# PSU_DRIVE.net
KiCad netlist of a schematic drawn in Altium Designer
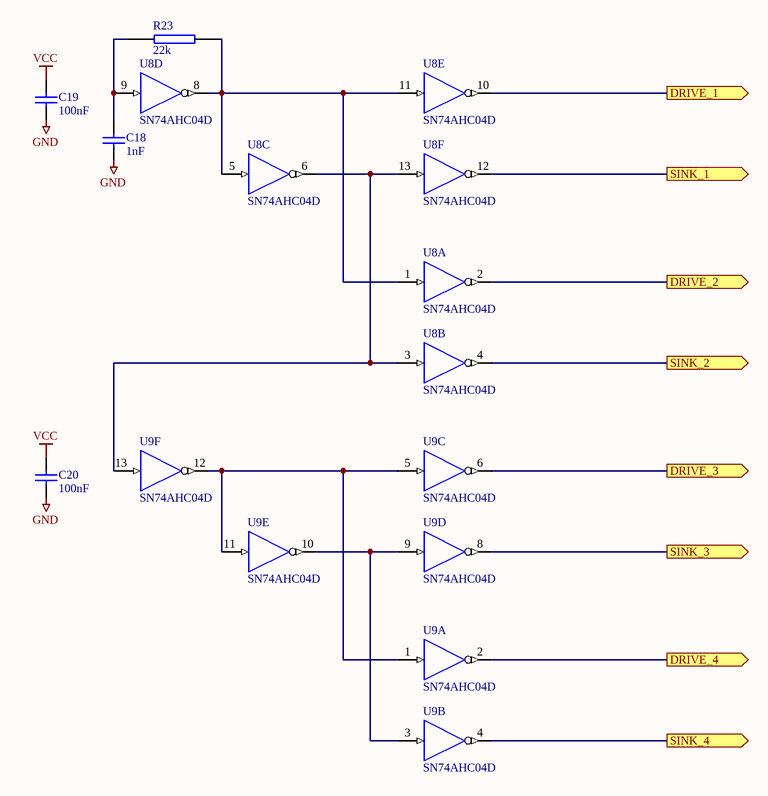
[diagram p0: PSU_DRIVE.SchDoc]

(export (version "E")
  (design (tool "Eeschema 10.0.6"))
  (components
    (comp (ref "C18")
      (value "1nF")
      (footprint "CAP (3D) - 0603")
      (description "Capacitor")
      (fields (field (name "Comment") "Cap") (field (name "PUBLISHER") "Altium Limited"))
      (libsource (lib "Miscellaneous Devices") (part "Cap"))
    )
    (comp (ref "C19")
      (value "100nF")
      (footprint "CAP (3D) - 0603")
      (description "Capacitor")
      (libsource (lib "Miscellaneous Devices") (part "Cap"))
    )
    (comp (ref "C20")
      (value "100nF")
      (footprint "CAP (3D) - 0603")
      (description "Capacitor")
      (libsource (lib "Miscellaneous Devices") (part "Cap"))
    )
    (comp (ref "R23")
      (value "22k")
      (footprint "RES (3D) - 0603")
      (description "RESISTOR SMD 0603 10k")
      (libsource (lib "NASCO Resistors") (part "RES SMD 0603 10k"))
    )
    (comp (ref "U8")
      (value "SN74AHC04D")
      (footprint "SOIC-14")
      (description "Hex Inverter")
      (fields (field (name "PUBLISHER") "Altium Limited"))
      (libsource (lib "TI Logic Gate 1") (part "SN74AHC04D"))
    )
    (comp (ref "U9")
      (value "SN74AHC04D")
      (footprint "SOIC-14")
      (description "Hex Inverter")
      (fields (field (name "PUBLISHER") "Altium Limited"))
      (libsource (lib "TI Logic Gate 1") (part "SN74AHC04D"))
    )
  )
  (nets
    (net (code "1") (name "/DRIVE_1") (class "Default")
      (node (ref "U8") (pin "10") (pinfunction "Y_10") (pintype "output"))
    )
    (net (code "2") (name "/DRIVE_2") (class "Default")
      (node (ref "U8") (pin "2") (pinfunction "Y_2") (pintype "output"))
    )
    (net (code "3") (name "/DRIVE_3") (class "Default")
      (node (ref "U9") (pin "6") (pinfunction "Y_6") (pintype "output"))
    )
    (net (code "4") (name "/DRIVE_4") (class "Default")
      (node (ref "U9") (pin "2") (pinfunction "Y_2") (pintype "output"))
    )
    (net (code "5") (name "/SINK_1") (class "Default")
      (node (ref "U8") (pin "12") (pinfunction "Y_12") (pintype "output"))
    )
    (net (code "6") (name "/SINK_2") (class "Default")
      (node (ref "U8") (pin "4") (pinfunction "Y_4") (pintype "output"))
    )
    (net (code "7") (name "/SINK_3") (class "Default")
      (node (ref "U9") (pin "8") (pinfunction "Y_8") (pintype "output"))
    )
    (net (code "8") (name "/SINK_4") (class "Default")
      (node (ref "U9") (pin "4") (pinfunction "Y_4") (pintype "output"))
    )
    (net (code "9") (name "GND") (class "Default")
      (node (ref "C18") (pin "2") (pinfunction "2_2") (pintype "passive"))
      (node (ref "C19") (pin "1") (pinfunction "1_1") (pintype "passive"))
      (node (ref "C20") (pin "1") (pinfunction "1_1") (pintype "passive"))
      (node (ref "U8") (pin "7") (pinfunction "GND_7") (pintype "power_in"))
      (node (ref "U9") (pin "7") (pinfunction "GND_7") (pintype "power_in"))
    )
    (net (code "10") (name "Net-(U8A-A)") (class "Default")
      (node (ref "R23") (pin "1") (pinfunction "1_1") (pintype "passive"))
      (node (ref "U8") (pin "1") (pinfunction "A_1") (pintype "input"))
      (node (ref "U8") (pin "11") (pinfunction "A_11") (pintype "input"))
      (node (ref "U8") (pin "5") (pinfunction "A_5") (pintype "input"))
      (node (ref "U8") (pin "8") (pinfunction "Y_8") (pintype "output"))
    )
    (net (code "11") (name "Net-(U8B-A)") (class "Default")
      (node (ref "U8") (pin "13") (pinfunction "A_13") (pintype "input"))
      (node (ref "U8") (pin "3") (pinfunction "A_3") (pintype "input"))
      (node (ref "U8") (pin "6") (pinfunction "Y_6") (pintype "output"))
      (node (ref "U9") (pin "13") (pinfunction "A_13") (pintype "input"))
    )
    (net (code "12") (name "Net-(U8D-A)") (class "Default")
      (node (ref "C18") (pin "1") (pinfunction "1_1") (pintype "passive"))
      (node (ref "R23") (pin "2") (pinfunction "2_2") (pintype "passive"))
      (node (ref "U8") (pin "9") (pinfunction "A_9") (pintype "input"))
    )
    (net (code "13") (name "Net-(U9A-A)") (class "Default")
      (node (ref "U9") (pin "1") (pinfunction "A_1") (pintype "input"))
      (node (ref "U9") (pin "11") (pinfunction "A_11") (pintype "input"))
      (node (ref "U9") (pin "12") (pinfunction "Y_12") (pintype "output"))
      (node (ref "U9") (pin "5") (pinfunction "A_5") (pintype "input"))
    )
    (net (code "14") (name "Net-(U9B-A)") (class "Default")
      (node (ref "U9") (pin "10") (pinfunction "Y_10") (pintype "output"))
      (node (ref "U9") (pin "3") (pinfunction "A_3") (pintype "input"))
      (node (ref "U9") (pin "9") (pinfunction "A_9") (pintype "input"))
    )
    (net (code "15") (name "VCC") (class "Default")
      (node (ref "C19") (pin "2") (pinfunction "2_2") (pintype "passive"))
      (node (ref "C20") (pin "2") (pinfunction "2_2") (pintype "passive"))
      (node (ref "U8") (pin "14") (pinfunction "VCC_14") (pintype "power_in"))
      (node (ref "U9") (pin "14") (pinfunction "VCC_14") (pintype "power_in"))
    )
  )
)
